# mic_usb_assy.net
KiCad netlist of a schematic drawn in Altium Designer
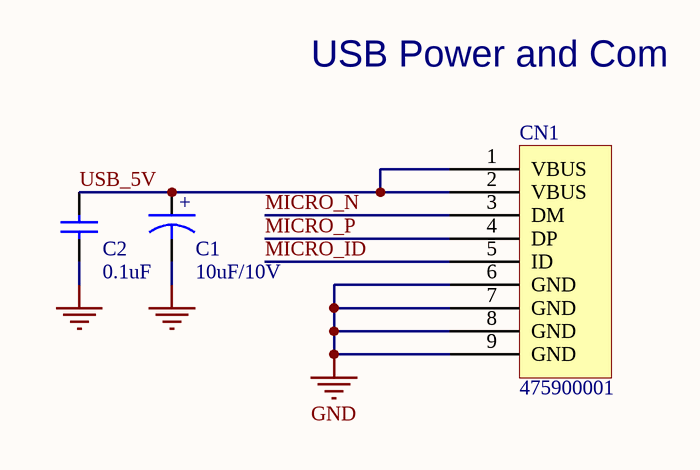
[diagram p0: mic_usb_assy.SchDoc]

(export (version "E")
  (design (tool "Eeschema 10.0.6"))
  (components
    (comp (ref "C1") (value "10uF/10V") (footprint "3216") (libsource (lib "MoJi LIB") (part "Capacitor")))
    (comp (ref "C2")
      (value "0.1uF")
      (footprint "0402C")
      (fields (field (name "PUBLISHER") "Altium Limited"))
      (libsource (lib "器件库") (part "Cap"))
    )
    (comp (ref "CN1")
      (value "475900001")
      (footprint "MICRO-USB-乐沪")
      (libsource (lib "mic_usb_assy FPC") (part "475900001"))
    )
  )
  (nets
    (net (code "1") (name "/MICRO_ID") (class "Default")
      (node (ref "CN1") (pin "5") (pinfunction "ID_5") (pintype "passive"))
    )
    (net (code "2") (name "/MICRO_N") (class "Default")
      (node (ref "CN1") (pin "3") (pinfunction "DM_3") (pintype "passive"))
    )
    (net (code "3") (name "/MICRO_P") (class "Default")
      (node (ref "CN1") (pin "4") (pinfunction "DP_4") (pintype "passive"))
    )
    (net (code "4") (name "/USB_5V") (class "Default")
      (node (ref "C1") (pin "1") (pinfunction "1_1") (pintype "passive"))
      (node (ref "C2") (pin "2") (pinfunction "2_2") (pintype "passive"))
      (node (ref "CN1") (pin "1") (pinfunction "VBUS_1") (pintype "passive"))
      (node (ref "CN1") (pin "2") (pinfunction "VBUS_2") (pintype "passive"))
    )
    (net (code "5") (name "GND") (class "Default")
      (node (ref "C1") (pin "2") (pinfunction "2_2") (pintype "passive"))
      (node (ref "C2") (pin "1") (pinfunction "1_1") (pintype "passive"))
      (node (ref "CN1") (pin "6") (pinfunction "GND_6") (pintype "passive"))
      (node (ref "CN1") (pin "7") (pinfunction "GND_7") (pintype "passive"))
      (node (ref "CN1") (pin "8") (pinfunction "GND_8") (pintype "passive"))
      (node (ref "CN1") (pin "9") (pinfunction "GND_9") (pintype "passive"))
    )
  )
)
